# ds1307.net
KiCad netlist of a schematic drawn in EAGLE
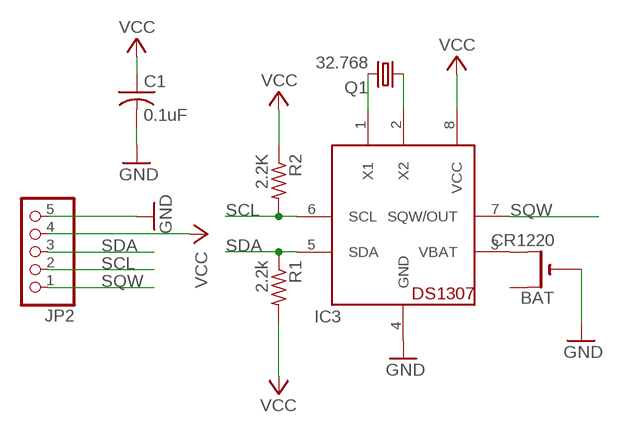
[diagram p0: schematic, sheet 1]

(export (version "E")
  (design (tool "Eeschema 10.0.6"))
  (components
    (comp (ref "BAT")
      (value "CR1220")
      (footprint "eagle-import:CR1220-THM")
      (libsource (lib "eagle-import") (part "CR1220THM"))
    )
    (comp (ref "C1")
      (value "0.1uF")
      (footprint "eagle-import:C025-025X050")
      (libsource (lib "eagle-import") (part "C-US025-025X050"))
    )
    (comp (ref "IC3")
      (value "DS1307")
      (footprint "eagle-import:DIL08")
      (libsource (lib "eagle-import") (part "DS1307"))
    )
    (comp (ref "JP2")
      (value "PINHD-1X5")
      (footprint "eagle-import:1X05")
      (libsource (lib "eagle-import") (part "PINHD-1X5"))
    )
    (comp (ref "Q1")
      (value "32.768")
      (footprint "eagle-import:TC38H")
      (libsource (lib "eagle-import") (part "CRYTALTC38H"))
    )
    (comp (ref "R1")
      (value "2.2k")
      (footprint "eagle-import:0207_10")
      (libsource (lib "eagle-import") (part "R-US_0207/10"))
    )
    (comp (ref "R2")
      (value "2.2K")
      (footprint "eagle-import:0207_10")
      (libsource (lib "eagle-import") (part "R-US_0207/10"))
    )
  )
  (nets
    (net (code "1") (name "/SCL") (class "Default")
      (node (ref "IC3") (pin "6") (pinfunction "SCL_6") (pintype "bidirectional"))
      (node (ref "JP2") (pin "2") (pinfunction "2_2") (pintype "passive"))
      (node (ref "R2") (pin "2") (pinfunction "2_2") (pintype "passive"))
    )
    (net (code "2") (name "/SDA") (class "Default")
      (node (ref "IC3") (pin "5") (pinfunction "SDA_5") (pintype "bidirectional"))
      (node (ref "JP2") (pin "3") (pinfunction "3_3") (pintype "passive"))
      (node (ref "R1") (pin "1") (pinfunction "1_1") (pintype "passive"))
    )
    (net (code "3") (name "/SQW") (class "Default")
      (node (ref "IC3") (pin "7") (pinfunction "SQW/OUT_7") (pintype "bidirectional"))
      (node (ref "JP2") (pin "1") (pinfunction "1_1") (pintype "passive"))
    )
    (net (code "4") (name "GND") (class "Default")
      (node (ref "BAT") (pin "-") (pinfunction "-_-") (pintype "passive"))
      (node (ref "C1") (pin "2") (pinfunction "2_2") (pintype "passive"))
      (node (ref "IC3") (pin "4") (pinfunction "GND_4") (pintype "power_in"))
      (node (ref "JP2") (pin "5") (pinfunction "5_5") (pintype "passive"))
    )
    (net (code "5") (name "Net-(BAT-+1)") (class "Default")
      (node (ref "BAT") (pin "+2") (pinfunction "+1_+2") (pintype "passive"))
      (node (ref "IC3") (pin "3") (pinfunction "VBAT_3") (pintype "power_in"))
    )
    (net (code "6") (name "Net-(IC3-X1)") (class "Default")
      (node (ref "IC3") (pin "1") (pinfunction "X1_1") (pintype "passive"))
      (node (ref "Q1") (pin "2") (pinfunction "2_2") (pintype "passive"))
    )
    (net (code "7") (name "Net-(IC3-X2)") (class "Default")
      (node (ref "IC3") (pin "2") (pinfunction "X2_2") (pintype "passive"))
      (node (ref "Q1") (pin "1") (pinfunction "1_1") (pintype "passive"))
    )
    (net (code "8") (name "VCC") (class "Default")
      (node (ref "C1") (pin "1") (pinfunction "1_1") (pintype "passive"))
      (node (ref "IC3") (pin "8") (pinfunction "VCC_8") (pintype "power_in"))
      (node (ref "JP2") (pin "4") (pinfunction "4_4") (pintype "passive"))
      (node (ref "R1") (pin "2") (pinfunction "2_2") (pintype "passive"))
      (node (ref "R2") (pin "1") (pinfunction "1_1") (pintype "passive"))
    )
    (net (code "9") (name "unconnected-(BAT-+-Pad+1)") (class "Default")
      (node (ref "BAT") (pin "+1") (pinfunction "+_+1") (pintype "passive"))
    )
  )
)
